# LWIR_FPGA_Misc.net
KiCad netlist of a schematic drawn in Altium Designer
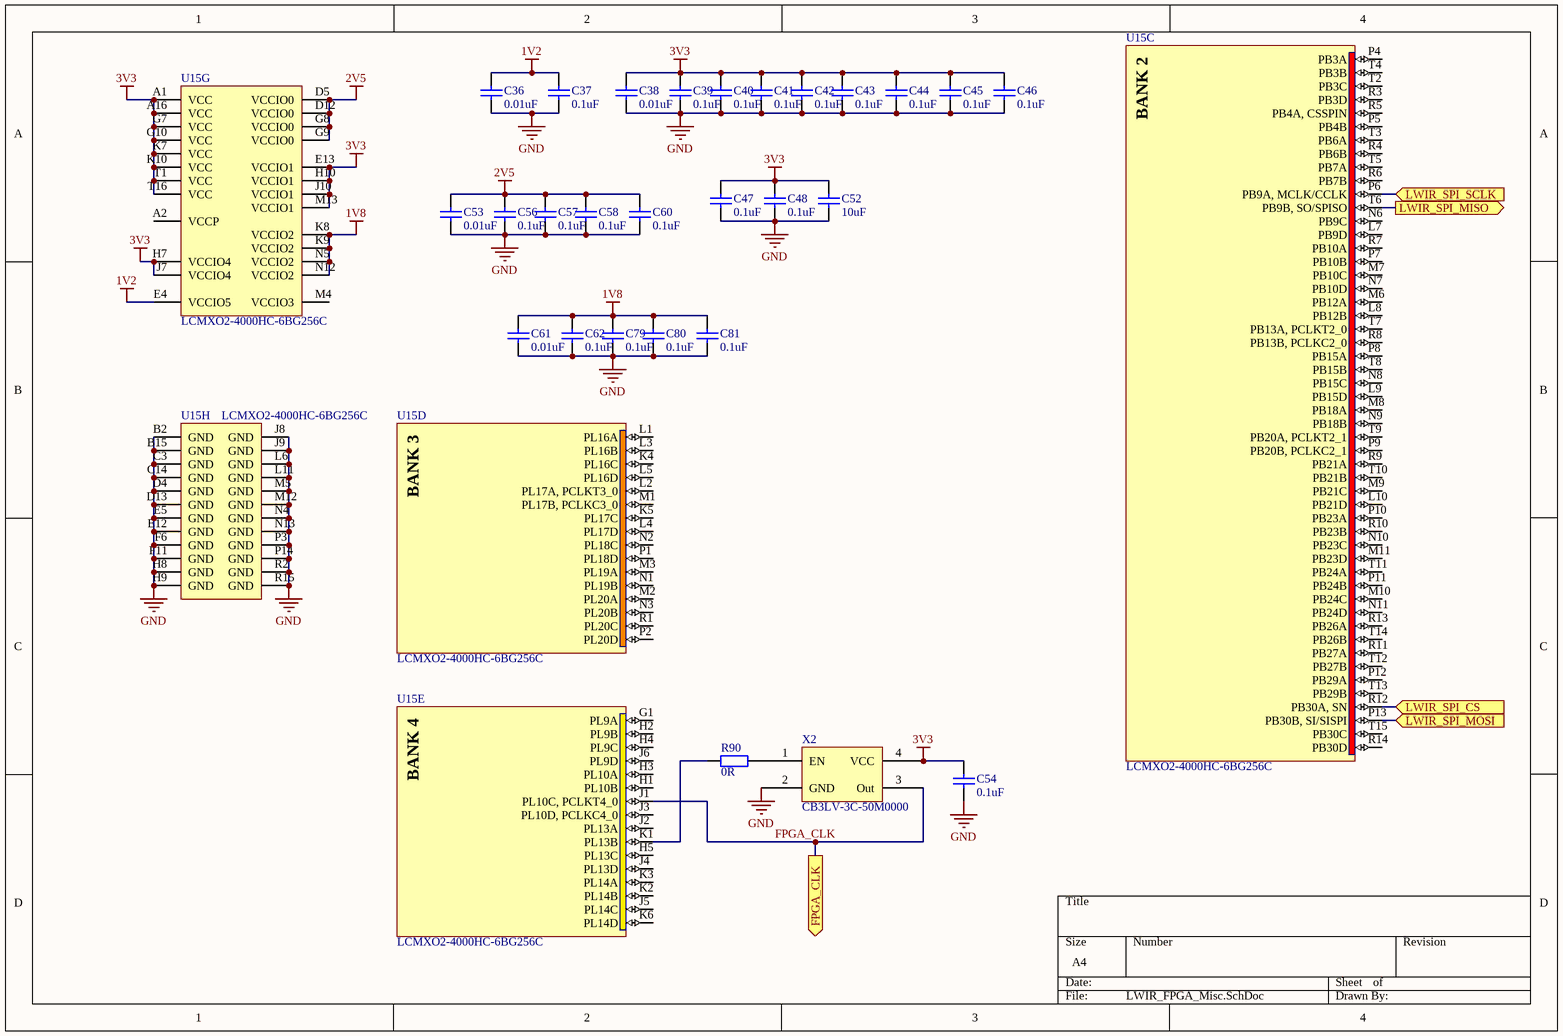
[diagram p0: LWIR_FPGA_Misc.SchDoc]

(export (version "E")
  (design (tool "Eeschema 10.0.6"))
  (components
    (comp (ref "C36")
      (value "0.01uF")
      (footprint "0402C_M")
      (description "CAP CER 0.01uF 50V X7R 0402")
      (fields
        (field (name "MANUFACTURER") "Murata Electronics North America")
        (field (name "MANUFACTURER PART NUMBER") "GRM155R71H103KA88D")
      )
      (libsource (lib "KMTI-main") (part "GRM155R71H103KA88D"))
    )
    (comp (ref "C37")
      (value "GRM155R71C104KA88D")
      (footprint "0402C_M")
      (description "CAP CER 0.1UF 16V X7R 0402")
      (fields
        (field (name "MANUFACTURER") "Murata Electronics North America")
        (field (name "TOLERANCE") "±10%")
        (field (name "CAPACITANCE") "0.1uF")
      )
      (libsource (lib "KMTI-main") (part "GRM155R71C104KA88D"))
    )
    (comp (ref "C38")
      (value "0.01uF")
      (footprint "0402C_M")
      (description "CAP CER 0.01uF 50V X7R 0402")
      (fields
        (field (name "MANUFACTURER") "Murata Electronics North America")
        (field (name "MANUFACTURER PART NUMBER") "GRM155R71H103KA88D")
      )
      (libsource (lib "KMTI-main") (part "GRM155R71H103KA88D"))
    )
    (comp (ref "C39")
      (value "GRM155R71C104KA88D")
      (footprint "0402C_M")
      (description "CAP CER 0.1UF 16V X7R 0402")
      (fields
        (field (name "MANUFACTURER") "Murata Electronics North America")
        (field (name "TOLERANCE") "±10%")
        (field (name "CAPACITANCE") "0.1uF")
      )
      (libsource (lib "KMTI-main") (part "GRM155R71C104KA88D"))
    )
    (comp (ref "C40")
      (value "GRM155R71C104KA88D")
      (footprint "0402C_M")
      (description "CAP CER 0.1UF 16V X7R 0402")
      (fields
        (field (name "MANUFACTURER") "Murata Electronics North America")
        (field (name "TOLERANCE") "±10%")
        (field (name "CAPACITANCE") "0.1uF")
      )
      (libsource (lib "KMTI-main") (part "GRM155R71C104KA88D"))
    )
    (comp (ref "C41")
      (value "GRM155R71C104KA88D")
      (footprint "0402C_M")
      (description "CAP CER 0.1UF 16V X7R 0402")
      (fields
        (field (name "MANUFACTURER") "Murata Electronics North America")
        (field (name "TOLERANCE") "±10%")
        (field (name "CAPACITANCE") "0.1uF")
      )
      (libsource (lib "KMTI-main") (part "GRM155R71C104KA88D"))
    )
    (comp (ref "C42")
      (value "GRM155R71C104KA88D")
      (footprint "0402C_M")
      (description "CAP CER 0.1UF 16V X7R 0402")
      (fields
        (field (name "MANUFACTURER") "Murata Electronics North America")
        (field (name "TOLERANCE") "±10%")
        (field (name "CAPACITANCE") "0.1uF")
      )
      (libsource (lib "KMTI-main") (part "GRM155R71C104KA88D"))
    )
    (comp (ref "C43")
      (value "GRM155R71C104KA88D")
      (footprint "0402C_M")
      (description "CAP CER 0.1UF 16V X7R 0402")
      (fields
        (field (name "MANUFACTURER") "Murata Electronics North America")
        (field (name "TOLERANCE") "±10%")
        (field (name "CAPACITANCE") "0.1uF")
      )
      (libsource (lib "KMTI-main") (part "GRM155R71C104KA88D"))
    )
    (comp (ref "C44")
      (value "GRM155R71C104KA88D")
      (footprint "0402C_M")
      (description "CAP CER 0.1UF 16V X7R 0402")
      (fields
        (field (name "MANUFACTURER") "Murata Electronics North America")
        (field (name "TOLERANCE") "±10%")
        (field (name "CAPACITANCE") "0.1uF")
      )
      (libsource (lib "KMTI-main") (part "GRM155R71C104KA88D"))
    )
    (comp (ref "C45")
      (value "GRM155R71C104KA88D")
      (footprint "0402C_M")
      (description "CAP CER 0.1UF 16V X7R 0402")
      (fields
        (field (name "MANUFACTURER") "Murata Electronics North America")
        (field (name "TOLERANCE") "±10%")
        (field (name "CAPACITANCE") "0.1uF")
      )
      (libsource (lib "KMTI-main") (part "GRM155R71C104KA88D"))
    )
    (comp (ref "C46")
      (value "GRM155R71C104KA88D")
      (footprint "0402C_M")
      (description "CAP CER 0.1UF 16V X7R 0402")
      (fields
        (field (name "MANUFACTURER") "Murata Electronics North America")
        (field (name "TOLERANCE") "±10%")
        (field (name "CAPACITANCE") "0.1uF")
      )
      (libsource (lib "KMTI-main") (part "GRM155R71C104KA88D"))
    )
    (comp (ref "C47")
      (value "GRM155R71C104KA88D")
      (footprint "0402C_M")
      (description "CAP CER 0.1UF 16V X7R 0402")
      (fields
        (field (name "MANUFACTURER") "Murata Electronics North America")
        (field (name "TOLERANCE") "±10%")
        (field (name "CAPACITANCE") "0.1uF")
      )
      (libsource (lib "KMTI-main") (part "GRM155R71C104KA88D"))
    )
    (comp (ref "C48")
      (value "GRM155R71C104KA88D")
      (footprint "0402C_M")
      (description "CAP CER 0.1UF 16V X7R 0402")
      (fields
        (field (name "MANUFACTURER") "Murata Electronics North America")
        (field (name "TOLERANCE") "±10%")
        (field (name "CAPACITANCE") "0.1uF")
      )
      (libsource (lib "KMTI-main") (part "GRM155R71C104KA88D"))
    )
    (comp (ref "C52")
      (value "10uF")
      (footprint "0603C_M")
      (description "CAP CER 10UF 6.3V X5R 0603")
      (fields
        (field (name "MANUFACTURER") "Murata Electronics North America")
        (field (name "MANUFACTURER PART NUMBER") "GRM188R60J106ME47D")
      )
      (libsource (lib "KMTI-main") (part "GRM188R60J106ME47D"))
    )
    (comp (ref "C53")
      (value "0.01uF")
      (footprint "0402C_M")
      (description "CAP CER 0.01uF 50V X7R 0402")
      (fields
        (field (name "MANUFACTURER") "Murata Electronics North America")
        (field (name "MANUFACTURER PART NUMBER") "GRM155R71H103KA88D")
      )
      (libsource (lib "KMTI-main") (part "GRM155R71H103KA88D"))
    )
    (comp (ref "C54")
      (value "GRM155R71C104KA88D")
      (footprint "0402C_M")
      (description "CAP CER 0.1UF 16V X7R 0402")
      (fields
        (field (name "MANUFACTURER") "Murata Electronics North America")
        (field (name "TOLERANCE") "±10%")
        (field (name "CAPACITANCE") "0.1uF")
      )
      (libsource (lib "KMTI-main") (part "GRM155R71C104KA88D"))
    )
    (comp (ref "C56")
      (value "GRM155R71C104KA88D")
      (footprint "0402C_M")
      (description "CAP CER 0.1UF 16V X7R 0402")
      (fields
        (field (name "MANUFACTURER") "Murata Electronics North America")
        (field (name "TOLERANCE") "±10%")
        (field (name "CAPACITANCE") "0.1uF")
      )
      (libsource (lib "KMTI-main") (part "GRM155R71C104KA88D"))
    )
    (comp (ref "C57")
      (value "GRM155R71C104KA88D")
      (footprint "0402C_M")
      (description "CAP CER 0.1UF 16V X7R 0402")
      (fields
        (field (name "MANUFACTURER") "Murata Electronics North America")
        (field (name "TOLERANCE") "±10%")
        (field (name "CAPACITANCE") "0.1uF")
      )
      (libsource (lib "KMTI-main") (part "GRM155R71C104KA88D"))
    )
    (comp (ref "C58")
      (value "GRM155R71C104KA88D")
      (footprint "0402C_M")
      (description "CAP CER 0.1UF 16V X7R 0402")
      (fields
        (field (name "MANUFACTURER") "Murata Electronics North America")
        (field (name "TOLERANCE") "±10%")
        (field (name "CAPACITANCE") "0.1uF")
      )
      (libsource (lib "KMTI-main") (part "GRM155R71C104KA88D"))
    )
    (comp (ref "C60")
      (value "GRM155R71C104KA88D")
      (footprint "0402C_M")
      (description "CAP CER 0.1UF 16V X7R 0402")
      (fields
        (field (name "MANUFACTURER") "Murata Electronics North America")
        (field (name "TOLERANCE") "±10%")
        (field (name "CAPACITANCE") "0.1uF")
      )
      (libsource (lib "KMTI-main") (part "GRM155R71C104KA88D"))
    )
    (comp (ref "C61")
      (value "0.01uF")
      (footprint "0402C_M")
      (description "CAP CER 0.01uF 50V X7R 0402")
      (fields
        (field (name "MANUFACTURER") "Murata Electronics North America")
        (field (name "MANUFACTURER PART NUMBER") "GRM155R71H103KA88D")
      )
      (libsource (lib "KMTI-main") (part "GRM155R71H103KA88D"))
    )
    (comp (ref "C62")
      (value "GRM155R71C104KA88D")
      (footprint "0402C_M")
      (description "CAP CER 0.1UF 16V X7R 0402")
      (fields
        (field (name "MANUFACTURER") "Murata Electronics North America")
        (field (name "TOLERANCE") "±10%")
        (field (name "CAPACITANCE") "0.1uF")
      )
      (libsource (lib "KMTI-main") (part "GRM155R71C104KA88D"))
    )
    (comp (ref "C79")
      (value "GRM155R71C104KA88D")
      (footprint "0402C_M")
      (description "CAP CER 0.1UF 16V X7R 0402")
      (fields
        (field (name "MANUFACTURER") "Murata Electronics North America")
        (field (name "TOLERANCE") "±10%")
        (field (name "CAPACITANCE") "0.1uF")
      )
      (libsource (lib "KMTI-main") (part "GRM155R71C104KA88D"))
    )
    (comp (ref "C80")
      (value "GRM155R71C104KA88D")
      (footprint "0402C_M")
      (description "CAP CER 0.1UF 16V X7R 0402")
      (fields
        (field (name "MANUFACTURER") "Murata Electronics North America")
        (field (name "TOLERANCE") "±10%")
        (field (name "CAPACITANCE") "0.1uF")
      )
      (libsource (lib "KMTI-main") (part "GRM155R71C104KA88D"))
    )
    (comp (ref "C81")
      (value "GRM155R71C104KA88D")
      (footprint "0402C_M")
      (description "CAP CER 0.1UF 16V X7R 0402")
      (fields
        (field (name "MANUFACTURER") "Murata Electronics North America")
        (field (name "TOLERANCE") "±10%")
        (field (name "CAPACITANCE") "0.1uF")
      )
      (libsource (lib "KMTI-main") (part "GRM155R71C104KA88D"))
    )
    (comp (ref "R90")
      (value "0R")
      (footprint "0402R_M")
      (fields (field (name "Comment") "Generic resitor"))
      (libsource (lib "KMTI-main") (part "Resistor"))
    )
    (comp (ref "U15")
      (value "LCMXO2-4000HC-6BG256C")
      (footprint "caBGA256")
      (libsource (lib "Altium Content Vault") (part "PLD-LTMXO2-4000-GA256"))
    )
    (comp (ref "X2")
      (value "CB3LV-3C-50M0000")
      (footprint "CB3LV-3C-50M0000")
      (description "OSC XO 50.000MHZ HCMOS TTL SMD")
      (fields (field (name "MANUFACTURER") "CTS-Frequency Controls"))
      (libsource (lib "KMTI-main") (part "CB3LV-3C-50M0000"))
    )
  )
  (nets
    (net (code "1") (name "/FPGA_CLK") (class "Default")
      (node (ref "U15") (pin "J1") (pinfunction "PL10C,_PCLKT4_0_J1") (pintype "bidirectional"))
      (node (ref "X2") (pin "3") (pinfunction "Out_3") (pintype "passive"))
    )
    (net (code "2") (name "/LWIR_SPI_CS") (class "Default")
      (node (ref "U15") (pin "R12") (pinfunction "PB30A,_SN_R12") (pintype "bidirectional"))
    )
    (net (code "3") (name "/LWIR_SPI_MISO") (class "Default")
      (node (ref "U15") (pin "T6") (pinfunction "PB9B,_SO/SPISO_T6") (pintype "bidirectional"))
    )
    (net (code "4") (name "/LWIR_SPI_MOSI") (class "Default")
      (node (ref "U15") (pin "P13") (pinfunction "PB30B,_SI/SISPI_P13") (pintype "bidirectional"))
    )
    (net (code "5") (name "/LWIR_SPI_SCLK") (class "Default")
      (node (ref "U15") (pin "P6") (pinfunction "PB9A,_MCLK/CCLK_P6") (pintype "bidirectional"))
    )
    (net (code "6") (name "1V2") (class "Default")
      (node (ref "C36") (pin "2") (pinfunction "2_2") (pintype "passive"))
      (node (ref "C37") (pin "2") (pinfunction "2_2") (pintype "passive"))
      (node (ref "U15") (pin "E4") (pinfunction "VCCIO5_E4") (pintype "power_in"))
    )
    (net (code "7") (name "1V8") (class "Default")
      (node (ref "C61") (pin "2") (pinfunction "2_2") (pintype "passive"))
      (node (ref "C62") (pin "2") (pinfunction "2_2") (pintype "passive"))
      (node (ref "C79") (pin "2") (pinfunction "2_2") (pintype "passive"))
      (node (ref "C80") (pin "2") (pinfunction "2_2") (pintype "passive"))
      (node (ref "C81") (pin "2") (pinfunction "2_2") (pintype "passive"))
      (node (ref "U15") (pin "K8") (pinfunction "VCCIO2_K8") (pintype "power_in"))
      (node (ref "U15") (pin "K9") (pinfunction "VCCIO2_K9") (pintype "power_in"))
      (node (ref "U15") (pin "N12") (pinfunction "VCCIO2_N12") (pintype "power_in"))
      (node (ref "U15") (pin "N5") (pinfunction "VCCIO2_N5") (pintype "power_in"))
    )
    (net (code "8") (name "2V5") (class "Default")
      (node (ref "C53") (pin "2") (pinfunction "2_2") (pintype "passive"))
      (node (ref "C56") (pin "2") (pinfunction "2_2") (pintype "passive"))
      (node (ref "C57") (pin "2") (pinfunction "2_2") (pintype "passive"))
      (node (ref "C58") (pin "2") (pinfunction "2_2") (pintype "passive"))
      (node (ref "C60") (pin "2") (pinfunction "2_2") (pintype "passive"))
      (node (ref "U15") (pin "D12") (pinfunction "VCCIO0_D12") (pintype "power_in"))
      (node (ref "U15") (pin "D5") (pinfunction "VCCIO0_D5") (pintype "power_in"))
      (node (ref "U15") (pin "G8") (pinfunction "VCCIO0_G8") (pintype "power_in"))
      (node (ref "U15") (pin "G9") (pinfunction "VCCIO0_G9") (pintype "power_in"))
    )
    (net (code "9") (name "3V3") (class "Default")
      (node (ref "C38") (pin "2") (pinfunction "2_2") (pintype "passive"))
      (node (ref "C39") (pin "2") (pinfunction "2_2") (pintype "passive"))
      (node (ref "C40") (pin "2") (pinfunction "2_2") (pintype "passive"))
      (node (ref "C41") (pin "2") (pinfunction "2_2") (pintype "passive"))
      (node (ref "C42") (pin "2") (pinfunction "2_2") (pintype "passive"))
      (node (ref "C43") (pin "2") (pinfunction "2_2") (pintype "passive"))
      (node (ref "C44") (pin "2") (pinfunction "2_2") (pintype "passive"))
      (node (ref "C45") (pin "2") (pinfunction "2_2") (pintype "passive"))
      (node (ref "C46") (pin "2") (pinfunction "2_2") (pintype "passive"))
      (node (ref "C47") (pin "2") (pinfunction "2_2") (pintype "passive"))
      (node (ref "C48") (pin "2") (pinfunction "2_2") (pintype "passive"))
      (node (ref "C52") (pin "2") (pinfunction "2_2") (pintype "passive"))
      (node (ref "C54") (pin "2") (pinfunction "2_2") (pintype "passive"))
      (node (ref "U15") (pin "A1") (pinfunction "VCC_A1") (pintype "power_in"))
      (node (ref "U15") (pin "A16") (pinfunction "VCC_A16") (pintype "power_in"))
      (node (ref "U15") (pin "E13") (pinfunction "VCCIO1_E13") (pintype "power_in"))
      (node (ref "U15") (pin "G10") (pinfunction "VCC_G10") (pintype "power_in"))
      (node (ref "U15") (pin "G7") (pinfunction "VCC_G7") (pintype "power_in"))
      (node (ref "U15") (pin "H10") (pinfunction "VCCIO1_H10") (pintype "power_in"))
      (node (ref "U15") (pin "H7") (pinfunction "VCCIO4_H7") (pintype "power_in"))
      (node (ref "U15") (pin "J10") (pinfunction "VCCIO1_J10") (pintype "power_in"))
      (node (ref "U15") (pin "J7") (pinfunction "VCCIO4_J7") (pintype "power_in"))
      (node (ref "U15") (pin "K10") (pinfunction "VCC_K10") (pintype "power_in"))
      (node (ref "U15") (pin "K7") (pinfunction "VCC_K7") (pintype "power_in"))
      (node (ref "U15") (pin "M13") (pinfunction "VCCIO1_M13") (pintype "power_in"))
      (node (ref "U15") (pin "T1") (pinfunction "VCC_T1") (pintype "power_in"))
      (node (ref "U15") (pin "T16") (pinfunction "VCC_T16") (pintype "power_in"))
      (node (ref "X2") (pin "4") (pinfunction "VCC_4") (pintype "passive"))
    )
    (net (code "10") (name "GND") (class "Default")
      (node (ref "C36") (pin "1") (pinfunction "1_1") (pintype "passive"))
      (node (ref "C37") (pin "1") (pinfunction "1_1") (pintype "passive"))
      (node (ref "C38") (pin "1") (pinfunction "1_1") (pintype "passive"))
      (node (ref "C39") (pin "1") (pinfunction "1_1") (pintype "passive"))
      (node (ref "C40") (pin "1") (pinfunction "1_1") (pintype "passive"))
      (node (ref "C41") (pin "1") (pinfunction "1_1") (pintype "passive"))
      (node (ref "C42") (pin "1") (pinfunction "1_1") (pintype "passive"))
      (node (ref "C43") (pin "1") (pinfunction "1_1") (pintype "passive"))
      (node (ref "C44") (pin "1") (pinfunction "1_1") (pintype "passive"))
      (node (ref "C45") (pin "1") (pinfunction "1_1") (pintype "passive"))
      (node (ref "C46") (pin "1") (pinfunction "1_1") (pintype "passive"))
      (node (ref "C47") (pin "1") (pinfunction "1_1") (pintype "passive"))
      (node (ref "C48") (pin "1") (pinfunction "1_1") (pintype "passive"))
      (node (ref "C52") (pin "1") (pinfunction "1_1") (pintype "passive"))
      (node (ref "C53") (pin "1") (pinfunction "1_1") (pintype "passive"))
      (node (ref "C54") (pin "1") (pinfunction "1_1") (pintype "passive"))
      (node (ref "C56") (pin "1") (pinfunction "1_1") (pintype "passive"))
      (node (ref "C57") (pin "1") (pinfunction "1_1") (pintype "passive"))
      (node (ref "C58") (pin "1") (pinfunction "1_1") (pintype "passive"))
      (node (ref "C60") (pin "1") (pinfunction "1_1") (pintype "passive"))
      (node (ref "C61") (pin "1") (pinfunction "1_1") (pintype "passive"))
      (node (ref "C62") (pin "1") (pinfunction "1_1") (pintype "passive"))
      (node (ref "C79") (pin "1") (pinfunction "1_1") (pintype "passive"))
      (node (ref "C80") (pin "1") (pinfunction "1_1") (pintype "passive"))
      (node (ref "C81") (pin "1") (pinfunction "1_1") (pintype "passive"))
      (node (ref "U15") (pin "B15") (pinfunction "GND_B15") (pintype "power_in"))
      (node (ref "U15") (pin "B2") (pinfunction "GND_B2") (pintype "power_in"))
      (node (ref "U15") (pin "C14") (pinfunction "GND_C14") (pintype "power_in"))
      (node (ref "U15") (pin "C3") (pinfunction "GND_C3") (pintype "power_in"))
      (node (ref "U15") (pin "D13") (pinfunction "GND_D13") (pintype "power_in"))
      (node (ref "U15") (pin "D4") (pinfunction "GND_D4") (pintype "power_in"))
      (node (ref "U15") (pin "E12") (pinfunction "GND_E12") (pintype "power_in"))
      (node (ref "U15") (pin "E5") (pinfunction "GND_E5") (pintype "power_in"))
      (node (ref "U15") (pin "F11") (pinfunction "GND_F11") (pintype "power_in"))
      (node (ref "U15") (pin "F6") (pinfunction "GND_F6") (pintype "power_in"))
      (node (ref "U15") (pin "H8") (pinfunction "GND_H8") (pintype "power_in"))
      (node (ref "U15") (pin "H9") (pinfunction "GND_H9") (pintype "power_in"))
      (node (ref "U15") (pin "J8") (pinfunction "GND_J8") (pintype "power_in"))
      (node (ref "U15") (pin "J9") (pinfunction "GND_J9") (pintype "power_in"))
      (node (ref "U15") (pin "L11") (pinfunction "GND_L11") (pintype "power_in"))
      (node (ref "U15") (pin "L6") (pinfunction "GND_L6") (pintype "power_in"))
      (node (ref "U15") (pin "M12") (pinfunction "GND_M12") (pintype "power_in"))
      (node (ref "U15") (pin "M5") (pinfunction "GND_M5") (pintype "power_in"))
      (node (ref "U15") (pin "N13") (pinfunction "GND_N13") (pintype "power_in"))
      (node (ref "U15") (pin "N4") (pinfunction "GND_N4") (pintype "power_in"))
      (node (ref "U15") (pin "P14") (pinfunction "GND_P14") (pintype "power_in"))
      (node (ref "U15") (pin "P3") (pinfunction "GND_P3") (pintype "power_in"))
      (node (ref "U15") (pin "R15") (pinfunction "GND_R15") (pintype "power_in"))
      (node (ref "U15") (pin "R2") (pinfunction "GND_R2") (pintype "power_in"))
      (node (ref "X2") (pin "2") (pinfunction "GND_2") (pintype "passive"))
    )
    (net (code "11") (name "Net-(U15E-PL13B)") (class "Default")
      (node (ref "R90") (pin "1") (pinfunction "1_1") (pintype "passive"))
      (node (ref "U15") (pin "K1") (pinfunction "PL13B_K1") (pintype "bidirectional"))
    )
    (net (code "12") (name "Net-(X2-EN)") (class "Default")
      (node (ref "R90") (pin "2") (pinfunction "2_2") (pintype "passive"))
      (node (ref "X2") (pin "1") (pinfunction "EN_1") (pintype "passive"))
    )
    (net (code "13") (name "unconnected-(U15C-PB3A-PadP4)") (class "Default")
      (node (ref "U15") (pin "P4") (pinfunction "PB3A_P4") (pintype "bidirectional"))
    )
    (net (code "14") (name "unconnected-(U15C-PB3B-PadT4)") (class "Default")
      (node (ref "U15") (pin "T4") (pinfunction "PB3B_T4") (pintype "bidirectional"))
    )
    (net (code "15") (name "unconnected-(U15C-PB3C-PadT2)") (class "Default")
      (node (ref "U15") (pin "T2") (pinfunction "PB3C_T2") (pintype "bidirectional"))
    )
    (net (code "16") (name "unconnected-(U15C-PB3D-PadR3)") (class "Default")
      (node (ref "U15") (pin "R3") (pinfunction "PB3D_R3") (pintype "bidirectional"))
    )
    (net (code "17") (name "unconnected-(U15C-PB4A,_CSSPIN-PadR5)") (class "Default")
      (node (ref "U15") (pin "R5") (pinfunction "PB4A,_CSSPIN_R5") (pintype "bidirectional"))
    )
    (net (code "18") (name "unconnected-(U15C-PB4B-PadP5)") (class "Default")
      (node (ref "U15") (pin "P5") (pinfunction "PB4B_P5") (pintype "bidirectional"))
    )
    (net (code "19") (name "unconnected-(U15C-PB6A-PadT3)") (class "Default")
      (node (ref "U15") (pin "T3") (pinfunction "PB6A_T3") (pintype "bidirectional"))
    )
    (net (code "20") (name "unconnected-(U15C-PB6B-PadR4)") (class "Default")
      (node (ref "U15") (pin "R4") (pinfunction "PB6B_R4") (pintype "bidirectional"))
    )
    (net (code "21") (name "unconnected-(U15C-PB7A-PadT5)") (class "Default")
      (node (ref "U15") (pin "T5") (pinfunction "PB7A_T5") (pintype "bidirectional"))
    )
    (net (code "22") (name "unconnected-(U15C-PB7B-PadR6)") (class "Default")
      (node (ref "U15") (pin "R6") (pinfunction "PB7B_R6") (pintype "bidirectional"))
    )
    (net (code "23") (name "unconnected-(U15C-PB9C-PadN6)") (class "Default")
      (node (ref "U15") (pin "N6") (pinfunction "PB9C_N6") (pintype "bidirectional"))
    )
    (net (code "24") (name "unconnected-(U15C-PB9D-PadL7)") (class "Default")
      (node (ref "U15") (pin "L7") (pinfunction "PB9D_L7") (pintype "bidirectional"))
    )
    (net (code "25") (name "unconnected-(U15C-PB10A-PadR7)") (class "Default")
      (node (ref "U15") (pin "R7") (pinfunction "PB10A_R7") (pintype "bidirectional"))
    )
    (net (code "26") (name "unconnected-(U15C-PB10B-PadP7)") (class "Default")
      (node (ref "U15") (pin "P7") (pinfunction "PB10B_P7") (pintype "bidirectional"))
    )
    (net (code "27") (name "unconnected-(U15C-PB10C-PadM7)") (class "Default")
      (node (ref "U15") (pin "M7") (pinfunction "PB10C_M7") (pintype "bidirectional"))
    )
    (net (code "28") (name "unconnected-(U15C-PB10D-PadN7)") (class "Default")
      (node (ref "U15") (pin "N7") (pinfunction "PB10D_N7") (pintype "bidirectional"))
    )
    (net (code "29") (name "unconnected-(U15C-PB12A-PadM6)") (class "Default")
      (node (ref "U15") (pin "M6") (pinfunction "PB12A_M6") (pintype "bidirectional"))
    )
    (net (code "30") (name "unconnected-(U15C-PB12B-PadL8)") (class "Default")
      (node (ref "U15") (pin "L8") (pinfunction "PB12B_L8") (pintype "bidirectional"))
    )
    (net (code "31") (name "unconnected-(U15C-PB13A,_PCLKT2_0-PadT7)") (class "Default")
      (node (ref "U15") (pin "T7") (pinfunction "PB13A,_PCLKT2_0_T7") (pintype "bidirectional"))
    )
    (net (code "32") (name "unconnected-(U15C-PB13B,_PCLKC2_0-PadR8)") (class "Default")
      (node (ref "U15") (pin "R8") (pinfunction "PB13B,_PCLKC2_0_R8") (pintype "bidirectional"))
    )
    (net (code "33") (name "unconnected-(U15C-PB15A-PadP8)") (class "Default")
      (node (ref "U15") (pin "P8") (pinfunction "PB15A_P8") (pintype "bidirectional"))
    )
    (net (code "34") (name "unconnected-(U15C-PB15B-PadT8)") (class "Default")
      (node (ref "U15") (pin "T8") (pinfunction "PB15B_T8") (pintype "bidirectional"))
    )
    (net (code "35") (name "unconnected-(U15C-PB15C-PadN8)") (class "Default")
      (node (ref "U15") (pin "N8") (pinfunction "PB15C_N8") (pintype "bidirectional"))
    )
    (net (code "36") (name "unconnected-(U15C-PB15D-PadL9)") (class "Default")
      (node (ref "U15") (pin "L9") (pinfunction "PB15D_L9") (pintype "bidirectional"))
    )
    (net (code "37") (name "unconnected-(U15C-PB18A-PadM8)") (class "Default")
      (node (ref "U15") (pin "M8") (pinfunction "PB18A_M8") (pintype "bidirectional"))
    )
    (net (code "38") (name "unconnected-(U15C-PB18B-PadN9)") (class "Default")
      (node (ref "U15") (pin "N9") (pinfunction "PB18B_N9") (pintype "bidirectional"))
    )
    (net (code "39") (name "unconnected-(U15C-PB20A,_PCLKT2_1-PadT9)") (class "Default")
      (node (ref "U15") (pin "T9") (pinfunction "PB20A,_PCLKT2_1_T9") (pintype "bidirectional"))
    )
    (net (code "40") (name "unconnected-(U15C-PB20B,_PCLKC2_1-PadP9)") (class "Default")
      (node (ref "U15") (pin "P9") (pinfunction "PB20B,_PCLKC2_1_P9") (pintype "bidirectional"))
    )
    (net (code "41") (name "unconnected-(U15C-PB21A-PadR9)") (class "Default")
      (node (ref "U15") (pin "R9") (pinfunction "PB21A_R9") (pintype "bidirectional"))
    )
    (net (code "42") (name "unconnected-(U15C-PB21B-PadT10)") (class "Default")
      (node (ref "U15") (pin "T10") (pinfunction "PB21B_T10") (pintype "bidirectional"))
    )
    (net (code "43") (name "unconnected-(U15C-PB21C-PadM9)") (class "Default")
      (node (ref "U15") (pin "M9") (pinfunction "PB21C_M9") (pintype "bidirectional"))
    )
    (net (code "44") (name "unconnected-(U15C-PB21D-PadL10)") (class "Default")
      (node (ref "U15") (pin "L10") (pinfunction "PB21D_L10") (pintype "bidirectional"))
    )
    (net (code "45") (name "unconnected-(U15C-PB23A-PadP10)") (class "Default")
      (node (ref "U15") (pin "P10") (pinfunction "PB23A_P10") (pintype "bidirectional"))
    )
    (net (code "46") (name "unconnected-(U15C-PB23B-PadR10)") (class "Default")
      (node (ref "U15") (pin "R10") (pinfunction "PB23B_R10") (pintype "bidirectional"))
    )
    (net (code "47") (name "unconnected-(U15C-PB23C-PadN10)") (class "Default")
      (node (ref "U15") (pin "N10") (pinfunction "PB23C_N10") (pintype "bidirectional"))
    )
    (net (code "48") (name "unconnected-(U15C-PB23D-PadM11)") (class "Default")
      (node (ref "U15") (pin "M11") (pinfunction "PB23D_M11") (pintype "bidirectional"))
    )
    (net (code "49") (name "unconnected-(U15C-PB24A-PadT11)") (class "Default")
      (node (ref "U15") (pin "T11") (pinfunction "PB24A_T11") (pintype "bidirectional"))
    )
    (net (code "50") (name "unconnected-(U15C-PB24B-PadP11)") (class "Default")
      (node (ref "U15") (pin "P11") (pinfunction "PB24B_P11") (pintype "bidirectional"))
    )
    (net (code "51") (name "unconnected-(U15C-PB24C-PadM10)") (class "Default")
      (node (ref "U15") (pin "M10") (pinfunction "PB24C_M10") (pintype "bidirectional"))
    )
    (net (code "52") (name "unconnected-(U15C-PB24D-PadN11)") (class "Default")
      (node (ref "U15") (pin "N11") (pinfunction "PB24D_N11") (pintype "bidirectional"))
    )
    (net (code "53") (name "unconnected-(U15C-PB26A-PadR13)") (class "Default")
      (node (ref "U15") (pin "R13") (pinfunction "PB26A_R13") (pintype "bidirectional"))
    )
    (net (code "54") (name "unconnected-(U15C-PB26B-PadT14)") (class "Default")
      (node (ref "U15") (pin "T14") (pinfunction "PB26B_T14") (pintype "bidirectional"))
    )
    (net (code "55") (name "unconnected-(U15C-PB27A-PadR11)") (class "Default")
      (node (ref "U15") (pin "R11") (pinfunction "PB27A_R11") (pintype "bidirectional"))
    )
    (net (code "56") (name "unconnected-(U15C-PB27B-PadT12)") (class "Default")
      (node (ref "U15") (pin "T12") (pinfunction "PB27B_T12") (pintype "bidirectional"))
    )
    (net (code "57") (name "unconnected-(U15C-PB29A-PadP12)") (class "Default")
      (node (ref "U15") (pin "P12") (pinfunction "PB29A_P12") (pintype "bidirectional"))
    )
    (net (code "58") (name "unconnected-(U15C-PB29B-PadT13)") (class "Default")
      (node (ref "U15") (pin "T13") (pinfunction "PB29B_T13") (pintype "bidirectional"))
    )
    (net (code "59") (name "unconnected-(U15C-PB30C-PadT15)") (class "Default")
      (node (ref "U15") (pin "T15") (pinfunction "PB30C_T15") (pintype "bidirectional"))
    )
    (net (code "60") (name "unconnected-(U15C-PB30D-PadR14)") (class "Default")
      (node (ref "U15") (pin "R14") (pinfunction "PB30D_R14") (pintype "bidirectional"))
    )
    (net (code "61") (name "unconnected-(U15D-PL16A-PadL1)") (class "Default")
      (node (ref "U15") (pin "L1") (pinfunction "PL16A_L1") (pintype "bidirectional"))
    )
    (net (code "62") (name "unconnected-(U15D-PL16B-PadL3)") (class "Default")
      (node (ref "U15") (pin "L3") (pinfunction "PL16B_L3") (pintype "bidirectional"))
    )
    (net (code "63") (name "unconnected-(U15D-PL16C-PadK4)") (class "Default")
      (node (ref "U15") (pin "K4") (pinfunction "PL16C_K4") (pintype "bidirectional"))
    )
    (net (code "64") (name "unconnected-(U15D-PL16D-PadL5)") (class "Default")
      (node (ref "U15") (pin "L5") (pinfunction "PL16D_L5") (pintype "bidirectional"))
    )
    (net (code "65") (name "unconnected-(U15D-PL17A,_PCLKT3_0-PadL2)") (class "Default")
      (node (ref "U15") (pin "L2") (pinfunction "PL17A,_PCLKT3_0_L2") (pintype "bidirectional"))
    )
    (net (code "66") (name "unconnected-(U15D-PL17B,_PCLKC3_0-PadM1)") (class "Default")
      (node (ref "U15") (pin "M1") (pinfunction "PL17B,_PCLKC3_0_M1") (pintype "bidirectional"))
    )
    (net (code "67") (name "unconnected-(U15D-PL17C-PadK5)") (class "Default")
      (node (ref "U15") (pin "K5") (pinfunction "PL17C_K5") (pintype "bidirectional"))
    )
    (net (code "68") (name "unconnected-(U15D-PL17D-PadL4)") (class "Default")
      (node (ref "U15") (pin "L4") (pinfunction "PL17D_L4") (pintype "bidirectional"))
    )
    (net (code "69") (name "unconnected-(U15D-PL18C-PadN2)") (class "Default")
      (node (ref "U15") (pin "N2") (pinfunction "PL18C_N2") (pintype "bidirectional"))
    )
    (net (code "70") (name "unconnected-(U15D-PL18D-PadP1)") (class "Default")
      (node (ref "U15") (pin "P1") (pinfunction "PL18D_P1") (pintype "bidirectional"))
    )
    (net (code "71") (name "unconnected-(U15D-PL19A-PadM3)") (class "Default")
      (node (ref "U15") (pin "M3") (pinfunction "PL19A_M3") (pintype "bidirectional"))
    )
    (net (code "72") (name "unconnected-(U15D-PL19B-PadN1)") (class "Default")
      (node (ref "U15") (pin "N1") (pinfunction "PL19B_N1") (pintype "bidirectional"))
    )
    (net (code "73") (name "unconnected-(U15D-PL20A-PadM2)") (class "Default")
      (node (ref "U15") (pin "M2") (pinfunction "PL20A_M2") (pintype "bidirectional"))
    )
    (net (code "74") (name "unconnected-(U15D-PL20B-PadN3)") (class "Default")
      (node (ref "U15") (pin "N3") (pinfunction "PL20B_N3") (pintype "bidirectional"))
    )
    (net (code "75") (name "unconnected-(U15D-PL20C-PadR1)") (class "Default")
      (node (ref "U15") (pin "R1") (pinfunction "PL20C_R1") (pintype "bidirectional"))
    )
    (net (code "76") (name "unconnected-(U15D-PL20D-PadP2)") (class "Default")
      (node (ref "U15") (pin "P2") (pinfunction "PL20D_P2") (pintype "bidirectional"))
    )
    (net (code "77") (name "unconnected-(U15E-PL9A-PadG1)") (class "Default")
      (node (ref "U15") (pin "G1") (pinfunction "PL9A_G1") (pintype "bidirectional"))
    )
    (net (code "78") (name "unconnected-(U15E-PL9B-PadH2)") (class "Default")
      (node (ref "U15") (pin "H2") (pinfunction "PL9B_H2") (pintype "bidirectional"))
    )
    (net (code "79") (name "unconnected-(U15E-PL9C-PadH4)") (class "Default")
      (node (ref "U15") (pin "H4") (pinfunction "PL9C_H4") (pintype "bidirectional"))
    )
    (net (code "80") (name "unconnected-(U15E-PL9D-PadJ6)") (class "Default")
      (node (ref "U15") (pin "J6") (pinfunction "PL9D_J6") (pintype "bidirectional"))
    )
    (net (code "81") (name "unconnected-(U15E-PL10A-PadH3)") (class "Default")
      (node (ref "U15") (pin "H3") (pinfunction "PL10A_H3") (pintype "bidirectional"))
    )
    (net (code "82") (name "unconnected-(U15E-PL10B-PadH1)") (class "Default")
      (node (ref "U15") (pin "H1") (pinfunction "PL10B_H1") (pintype "bidirectional"))
    )
    (net (code "83") (name "unconnected-(U15E-PL10D,_PCLKC4_0-PadJ3)") (class "Default")
      (node (ref "U15") (pin "J3") (pinfunction "PL10D,_PCLKC4_0_J3") (pintype "bidirectional"))
    )
    (net (code "84") (name "unconnected-(U15E-PL13A-PadJ2)") (class "Default")
      (node (ref "U15") (pin "J2") (pinfunction "PL13A_J2") (pintype "bidirectional"))
    )
    (net (code "85") (name "unconnected-(U15E-PL13C-PadH5)") (class "Default")
      (node (ref "U15") (pin "H5") (pinfunction "PL13C_H5") (pintype "bidirectional"))
    )
    (net (code "86") (name "unconnected-(U15E-PL13D-PadJ4)") (class "Default")
      (node (ref "U15") (pin "J4") (pinfunction "PL13D_J4") (pintype "bidirectional"))
    )
    (net (code "87") (name "unconnected-(U15E-PL14A-PadK3)") (class "Default")
      (node (ref "U15") (pin "K3") (pinfunction "PL14A_K3") (pintype "bidirectional"))
    )
    (net (code "88") (name "unconnected-(U15E-PL14B-PadK2)") (class "Default")
      (node (ref "U15") (pin "K2") (pinfunction "PL14B_K2") (pintype "bidirectional"))
    )
    (net (code "89") (name "unconnected-(U15E-PL14C-PadJ5)") (class "Default")
      (node (ref "U15") (pin "J5") (pinfunction "PL14C_J5") (pintype "bidirectional"))
    )
    (net (code "90") (name "unconnected-(U15E-PL14D-PadK6)") (class "Default")
      (node (ref "U15") (pin "K6") (pinfunction "PL14D_K6") (pintype "bidirectional"))
    )
    (net (code "91") (name "unconnected-(U15G-VCCIO3-PadM4)") (class "Default")
      (node (ref "U15") (pin "M4") (pinfunction "VCCIO3_M4") (pintype "power_in"))
    )
    (net (code "92") (name "unconnected-(U15G-VCCP-PadA2)") (class "Default")
      (node (ref "U15") (pin "A2") (pinfunction "VCCP_A2") (pintype "power_in"))
    )
  )
)
